# Alimentacion.net
KiCad netlist of a schematic drawn in Altium Designer
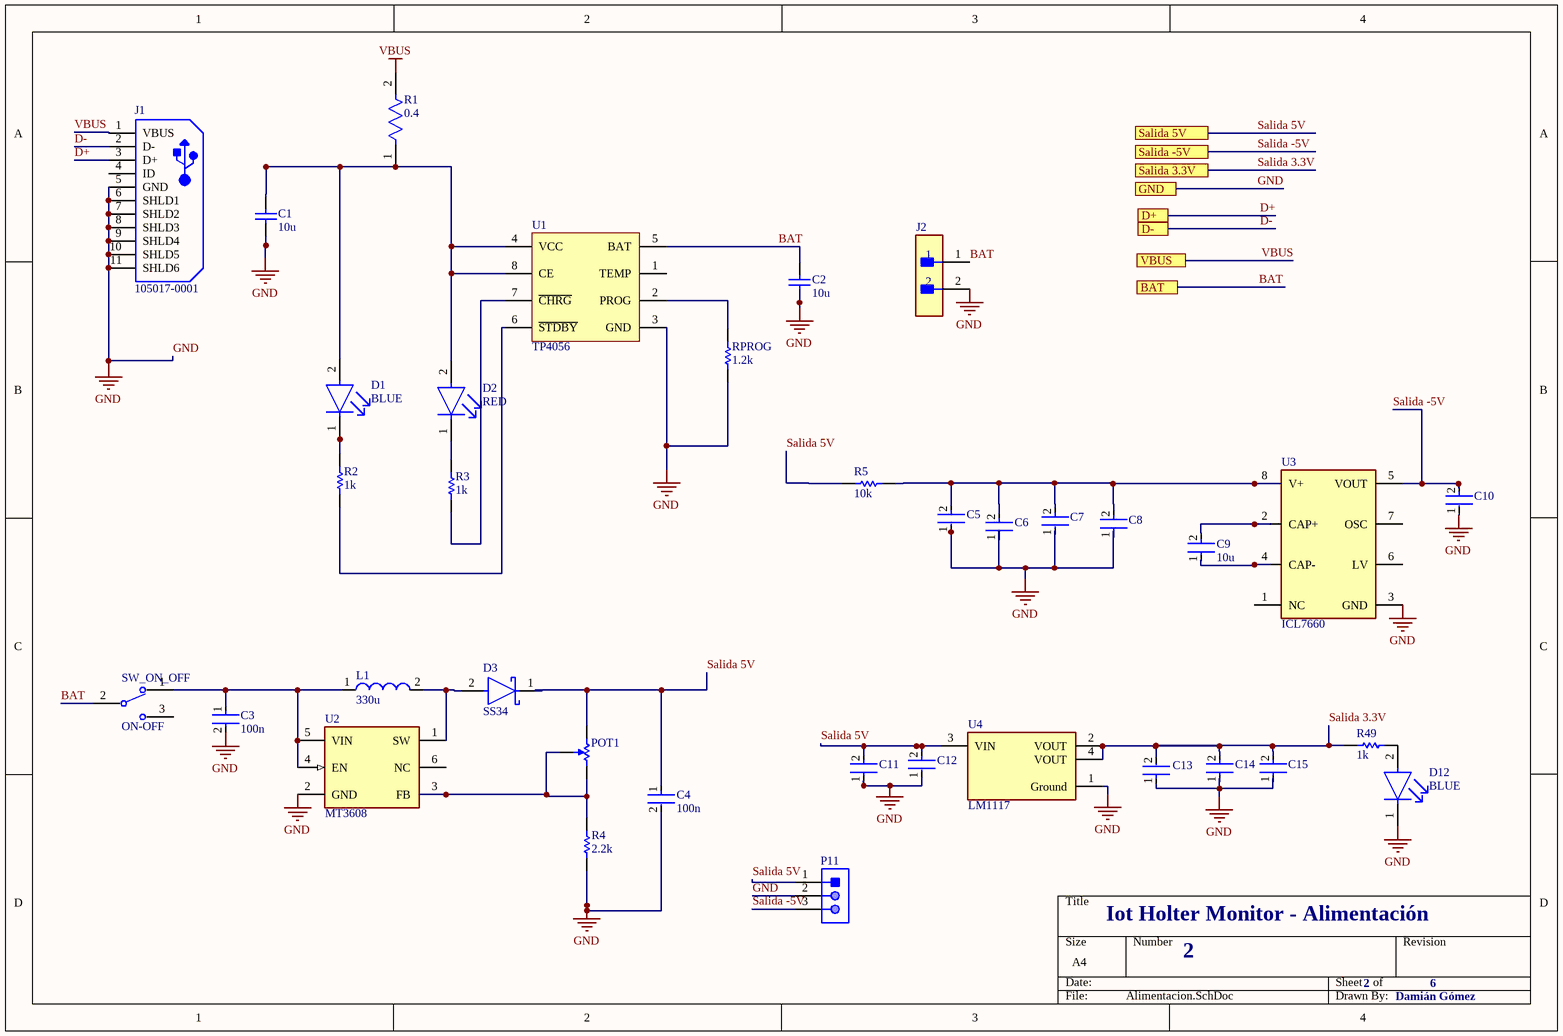
[diagram p0: Alimentacion.SchDoc]

(export (version "E")
  (design (tool "Eeschema 10.0.6"))
  (components
    (comp (ref "C1")
      (value "10u")
      (footprint "KEMT-1206-2_M")
      (description "CAP, Ceramic, 0.1 uF, +/- 10%, 50 V, -55 to 125 degC, 1206 (3216 Metric), RoHS, Tape and Reel")
      (fields (field (name "MANUFACTURER") "Kemet"))
      (libsource (lib "Altium Content Vault") (part "CAP-NP-2"))
    )
    (comp (ref "C2")
      (value "10u")
      (footprint "CAPC3216X190X55LL30T25")
      (description "Chip Capacitor, 10 uF, +/- 20%, 6.3 V, -55 to 85 degC, 1206 (3216 Metric), RoHS, Tape and Reel")
      (fields (field (name "TOLERANCE") "20%") (field (name "PARTNUMBER") "GRM31CR60J107ME39L"))
      (libsource (lib "Altium Content Vault") (part "CAP-NP-2"))
    )
    (comp (ref "C3")
      (value "100n")
      (footprint "FP-CL31-IPC_C")
      (description "Cap Ceramic 100nF 500V C0G ±5% SMD 1206 +125°C Embossed T/R")
      (fields (field (name "TOLERANCE") "5%"))
      (libsource (lib "Altium Content Vault") (part "b4654b650e69147ec39a6b967a45e02"))
    )
    (comp (ref "C4")
      (value "100n")
      (footprint "FP-CL31-IPC_C")
      (description "Cap Ceramic 100nF 500V C0G ±5% SMD 1206 +125°C Embossed T/R")
      (fields (field (name "TOLERANCE") "5%"))
      (libsource (lib "Altium Content Vault") (part "b4654b650e69147ec39a6b967a45e02"))
    )
    (comp (ref "C5")
      (value "GRM2165C1H332JA01D")
      (footprint "FP-GRM216-0_1-IPC_B")
      (description "Chip Multilayer Ceramic Capacitors for General Purpose, 0805, 3300pF, C0G, 30ppm/°C, 5%, 50V")
      (fields (field (name "VOLTAGE") "50V") (field (name "TOLERANCE") "5%"))
      (libsource (lib "Altium Content Vault") (part "236180d848d6139a670b325ea6854c9"))
    )
    (comp (ref "C6")
      (value "GRM2165C1H332JA01D")
      (footprint "FP-GRM216-0_1-IPC_B")
      (description "Chip Multilayer Ceramic Capacitors for General Purpose, 0805, 3300pF, C0G, 30ppm/°C, 5%, 50V")
      (fields (field (name "VOLTAGE") "50V") (field (name "TOLERANCE") "5%"))
      (libsource (lib "Altium Content Vault") (part "236180d848d6139a670b325ea6854c9"))
    )
    (comp (ref "C7")
      (value "GRM2165C1H332JA01D")
      (footprint "FP-GRM216-0_1-IPC_B")
      (description "Chip Multilayer Ceramic Capacitors for General Purpose, 0805, 3300pF, C0G, 30ppm/°C, 5%, 50V")
      (fields (field (name "VOLTAGE") "50V") (field (name "TOLERANCE") "5%"))
      (libsource (lib "Altium Content Vault") (part "236180d848d6139a670b325ea6854c9"))
    )
    (comp (ref "C8")
      (value "GRM2165C1H332JA01D")
      (footprint "FP-GRM216-0_1-IPC_B")
      (description "Chip Multilayer Ceramic Capacitors for General Purpose, 0805, 3300pF, C0G, 30ppm/°C, 5%, 50V")
      (fields (field (name "VOLTAGE") "50V") (field (name "TOLERANCE") "5%"))
      (libsource (lib "Altium Content Vault") (part "236180d848d6139a670b325ea6854c9"))
    )
    (comp (ref "C9")
      (value "10u")
      (footprint "FP-GRM216-0_1-IPC_B")
      (description "Chip Multilayer Ceramic Capacitors for General Purpose, 0805, 3300pF, C0G, 30ppm/°C, 5%, 50V")
      (fields (field (name "VOLTAGE") "50V") (field (name "TOLERANCE") "5%"))
      (libsource (lib "Altium Content Vault") (part "236180d848d6139a670b325ea6854c9"))
    )
    (comp (ref "C10")
      (value "GRM2165C1H332JA01D")
      (footprint "FP-GRM216-0_1-IPC_B")
      (description "Chip Multilayer Ceramic Capacitors for General Purpose, 0805, 3300pF, C0G, 30ppm/°C, 5%, 50V")
      (fields (field (name "VOLTAGE") "50V") (field (name "TOLERANCE") "5%"))
      (libsource (lib "Altium Content Vault") (part "236180d848d6139a670b325ea6854c9"))
    )
    (comp (ref "C11")
      (value "GRM2165C1H332JA01D")
      (footprint "FP-GRM216-0_1-IPC_B")
      (description "Chip Multilayer Ceramic Capacitors for General Purpose, 0805, 3300pF, C0G, 30ppm/°C, 5%, 50V")
      (fields (field (name "VOLTAGE") "50V") (field (name "TOLERANCE") "5%"))
      (libsource (lib "Altium Content Vault") (part "236180d848d6139a670b325ea6854c9"))
    )
    (comp (ref "C12")
      (value "GRM2165C1H332JA01D")
      (footprint "FP-GRM216-0_1-IPC_B")
      (description "Chip Multilayer Ceramic Capacitors for General Purpose, 0805, 3300pF, C0G, 30ppm/°C, 5%, 50V")
      (fields (field (name "VOLTAGE") "50V") (field (name "TOLERANCE") "5%"))
      (libsource (lib "Altium Content Vault") (part "236180d848d6139a670b325ea6854c9"))
    )
    (comp (ref "C13")
      (value "10uF")
      (footprint "FP-CL31-IPC_C")
      (description "Cap Ceramic 10uF 500V C0G ±5% SMD 1206 +125°C Embossed T/R")
      (fields (field (name "TOLERANCE") "5%"))
      (libsource (lib "Altium Content Vault") (part "b4654b650e69147ec39a6b967a45e02"))
    )
    (comp (ref "C14")
      (value "GRM2165C1H332JA01D")
      (footprint "FP-GRM216-0_1-IPC_C")
      (description "Chip Multilayer Ceramic Capacitors for General Purpose, 0805, 3300pF, C0G, 30ppm/°C, 5%, 50V")
      (fields (field (name "VOLTAGE") "50V") (field (name "TOLERANCE") "5%"))
      (libsource (lib "Altium Content Vault") (part "236180d848d6139a670b325ea6854c9"))
    )
    (comp (ref "C15")
      (value "GRM2165C1H332JA01D")
      (footprint "FP-GRM216-0_1-IPC_C")
      (description "Chip Multilayer Ceramic Capacitors for General Purpose, 0805, 3300pF, C0G, 30ppm/°C, 5%, 50V")
      (fields (field (name "VOLTAGE") "50V") (field (name "TOLERANCE") "5%"))
      (libsource (lib "Altium Content Vault") (part "236180d848d6139a670b325ea6854c9"))
    )
    (comp (ref "D1")
      (value "BLUE")
      (footprint "FP-LTST-C191TBKT-MFG")
      (description "LED BLUE CLEAR CHIP SMD")
      (libsource (lib "Altium Content Vault") (part "8706943c75ba83719d021d2fdc84c58"))
    )
    (comp (ref "D2")
      (value "RED")
      (footprint "FP-LTST-C191TBKT-MFG")
      (description "LED BLUE CLEAR CHIP SMD")
      (libsource (lib "Altium Content Vault") (part "8706943c75ba83719d021d2fdc84c58"))
    )
    (comp (ref "D3")
      (value "SS34")
      (footprint "FP-95402-MFG")
      (description "DIODE SCHOTTKY 40V 3A DO214AB")
      (fields (field (name "MANUFACTURER") "Vishay") (field (name "MANUFACTURER PART NUMBER") "SS34-E3/57T"))
      (libsource (lib "Altium Content Vault") (part "1d6ec82d83fb6aee721767c19dac4b9"))
    )
    (comp (ref "D12")
      (value "BLUE")
      (footprint "FP-LTST-C191TBKT-MFG")
      (description "LED BLUE CLEAR CHIP SMD")
      (libsource (lib "Altium Content Vault") (part "8706943c75ba83719d021d2fdc84c58"))
    )
    (comp (ref "J1")
      (value "105017-0001")
      (footprint "USB-MICRO-B_V")
      (fields (field (name "MANUFACTURER") "Molex"))
      (libsource (lib "Altium Content Vault") (part "USB-5-6SHLD"))
    )
    (comp (ref "J2")
      (value "TSW-102-07-L-S")
      (footprint "FP-TSW-102-07-L-S-MFG")
      (description "CONN HEADER VERT 2POS 2.54MM")
      (libsource (lib "Altium Content Vault") (part "3bc925449376181038e59eaffc5286c"))
    )
    (comp (ref "L1")
      (value "330u")
      (footprint "WE-PD 1050")
      (description "SMD-Shielded Power Inductor WE-PD, L=330 µH")
      (fields (field (name "MANUFACTURER") "Wuerth Elektronik") (field (name "PARTNUMBER") "7447714331"))
      (libsource (lib "Altium Content Vault") (part "PAS-IND-INDUCTOR-2"))
    )
    (comp (ref "P11")
      (value "640456-3")
      (footprint "TECO-640456-3")
      (description "Male Header, Pitch 2.54 mm, 1 x 3 Position, Height 10.03 mm, Tail Length 3.56 mm, -55 to 105 degC")
      (fields (field (name "MANUFACTURER") "TE Connectivity"))
      (libsource (lib "Altium Content Vault") (part "CN-1P-M-R3"))
    )
    (comp (ref "POT1")
      (value "3386P-1-104LF")
      (footprint "BOUR-3386P")
      (fields (field (name "TOLERANCE") "10%") (field (name "MANUFACTURER") "Bourns"))
      (libsource (lib "Altium Content Vault") (part "RES-ADJ-3_A"))
    )
    (comp (ref "R1")
      (value "0.4")
      (footprint "FP-RC3216-MFG")
      (description "Res Thick Film 1206 1kΩ 5% 0.25W ±100ppm/°C Molded SMD T/R")
      (fields (field (name "TOLERANCE") "5%"))
      (libsource (lib "Altium Content Vault") (part "1029c3af85768c4190bb7ad29bc67b5"))
    )
    (comp (ref "R2")
      (value "1k")
      (footprint "RESC2013X50X30LL20T20")
      (fields (field (name "MANUFACTURER") "Vishay Dale") (field (name "PART NUMBER") "CRCW08050000Z0EA"))
      (libsource (lib "Altium Content Vault") (part "RES"))
    )
    (comp (ref "R3")
      (value "1k")
      (footprint "RESC2013X50X30LL20T20")
      (fields (field (name "MANUFACTURER") "Vishay Dale") (field (name "PART NUMBER") "CRCW08050000Z0EA"))
      (libsource (lib "Altium Content Vault") (part "RES"))
    )
    (comp (ref "R4")
      (value "2.2k")
      (footprint "RESC2013X50X30LL20T20")
      (fields (field (name "MANUFACTURER") "Vishay Dale") (field (name "PART NUMBER") "CRCW08050000Z0EA"))
      (libsource (lib "Altium Content Vault") (part "RES"))
    )
    (comp (ref "R5")
      (value "10k")
      (footprint "RESC2013X50X30LL20T20")
      (fields (field (name "MANUFACTURER") "Vishay Dale") (field (name "PART NUMBER") "CRCW08050000Z0EA"))
      (libsource (lib "Altium Content Vault") (part "RES"))
    )
    (comp (ref "R49")
      (value "1k")
      (footprint "RESC2013X50X30LL20T20")
      (fields (field (name "MANUFACTURER") "Vishay Dale") (field (name "PART NUMBER") "CRCW08050000Z0EA"))
      (libsource (lib "Altium Content Vault") (part "RES"))
    )
    (comp (ref "RPROG")
      (value "1.2k")
      (footprint "RESC2013X50X30LL20T20")
      (fields (field (name "MANUFACTURER") "Vishay Dale") (field (name "PART NUMBER") "CRCW08050000Z0EA"))
      (libsource (lib "Altium Content Vault") (part "RES"))
    )
    (comp (ref "SW_ON_OFF")
      (value "ON-OFF")
      (footprint "FP-1825115-1-MFG")
      (description "SWITCH SLIDE SPDT 250MA 125V")
      (fields
        (field (name "MANUFACTURER PART NUMBER") "1825115-1")
        (field (name "MANUFACTURER") "TE Connectivity")
      )
      (libsource (lib "Altium Content Vault") (part "ec4e4964ed0d2d669af15d5af94fda9"))
    )
    (comp (ref "U1")
      (value "TP4056")
      (footprint "LT-S8-8_N")
      (fields
        (field (name "MANUFACTURER") "Linear Technology")
        (field (name "PARTNUMBER") "LTC4002ES8-4.2#PBF")
      )
      (libsource (lib "Altium Content Vault") (part "LT-LTC4002-X-S8-8"))
    )
    (comp (ref "U2")
      (value "MT3608")
      (footprint "FP-SOT26_SC74R-MFG")
      (description "IC LED DRIVER RGLTR DIM SOT23-6")
      (fields
        (field (name "MANUFACTURER PART NUMBER") "AP3032KTR-G1")
        (field (name "OCTOPART") "https://octopart.com/ap3032ktr-g1-diodes+inc.-30954666")
      )
      (libsource (lib "Altium Content Vault") (part "3919cb25f4a0d6df43ad4561642b66f"))
    )
    (comp (ref "U3")
      (value "ICL7660")
      (footprint "FP-S8-4-MFG")
      (description "IC REG CHARG PUMP INV 20MA 8SOIC")
      (fields
        (field (name "MANUFACTURER PART NUMBER") "ICL7660ESA+")
        (field (name "MANUFACTURER") "Maxim Integrated")
      )
      (libsource (lib "Altium Content Vault") (part "e56b1e088fdcf266b110f64408d959f"))
    )
    (comp (ref "U4")
      (value "LM1117")
      (footprint "FP-AMS1117-IPC_C")
      (description "LDO Voltage Regulators 1A, 3.3V")
      (fields
        (field (name "MANUFACTURER PART NUMBER") "AMS1117-3.3")
        (field (name "OCTOPART") "https://octopart.com/ams1117-3.3-advanced+monolithic+systems-25899300")
      )
      (libsource (lib "Altium Content Vault") (part "8bdbb5f8e77002000e30dd2845d0354"))
    )
  )
  (nets
    (net (code "1") (name "/BAT") (class "Default")
      (node (ref "C2") (pin "2") (pinfunction "2_2") (pintype "passive"))
      (node (ref "J2") (pin "1") (pinfunction "1_1") (pintype "passive"))
      (node (ref "SW_ON_OFF") (pin "2") (pinfunction "2_2") (pintype "passive"))
      (node (ref "U1") (pin "5") (pinfunction "BAT_5") (pintype "passive"))
    )
    (net (code "2") (name "/D+") (class "Default")
      (node (ref "J1") (pin "3") (pinfunction "D+_3") (pintype "tri_state"))
    )
    (net (code "3") (name "/D-") (class "Default")
      (node (ref "J1") (pin "2") (pinfunction "D-_2") (pintype "tri_state"))
    )
    (net (code "4") (name "/Salida -5V") (class "Default")
      (node (ref "C10") (pin "2") (pinfunction "2_2") (pintype "passive"))
      (node (ref "P11") (pin "3") (pinfunction "3_3") (pintype "passive"))
      (node (ref "U3") (pin "5") (pinfunction "VOUT_5") (pintype "power_in"))
    )
    (net (code "5") (name "/Salida 3.3V") (class "Default")
      (node (ref "C13") (pin "2") (pinfunction "2_2") (pintype "passive"))
      (node (ref "C14") (pin "2") (pinfunction "2_2") (pintype "passive"))
      (node (ref "C15") (pin "2") (pinfunction "2_2") (pintype "passive"))
      (node (ref "R49") (pin "1") (pinfunction "1_1") (pintype "passive"))
      (node (ref "U4") (pin "2") (pinfunction "VOUT_2") (pintype "power_in"))
      (node (ref "U4") (pin "4") (pinfunction "VOUT_4") (pintype "power_in"))
    )
    (net (code "6") (name "/Salida 5V") (class "Default")
      (node (ref "C11") (pin "2") (pinfunction "2_2") (pintype "passive"))
      (node (ref "C12") (pin "2") (pinfunction "2_2") (pintype "passive"))
      (node (ref "C4") (pin "1") (pinfunction "1_1") (pintype "passive"))
      (node (ref "D3") (pin "1") (pinfunction "C_1") (pintype "passive"))
      (node (ref "P11") (pin "1") (pinfunction "1_1") (pintype "passive"))
      (node (ref "POT1") (pin "1") (pinfunction "1_1") (pintype "passive"))
      (node (ref "R5") (pin "1") (pinfunction "1_1") (pintype "passive"))
      (node (ref "U4") (pin "3") (pinfunction "VIN_3") (pintype "power_in"))
    )
    (net (code "7") (name "GND") (class "Default")
      (node (ref "C1") (pin "1") (pinfunction "1_1") (pintype "passive"))
      (node (ref "C10") (pin "1") (pinfunction "1_1") (pintype "passive"))
      (node (ref "C11") (pin "1") (pinfunction "1_1") (pintype "passive"))
      (node (ref "C12") (pin "1") (pinfunction "1_1") (pintype "passive"))
      (node (ref "C13") (pin "1") (pinfunction "1_1") (pintype "passive"))
      (node (ref "C14") (pin "1") (pinfunction "1_1") (pintype "passive"))
      (node (ref "C15") (pin "1") (pinfunction "1_1") (pintype "passive"))
      (node (ref "C2") (pin "1") (pinfunction "1_1") (pintype "passive"))
      (node (ref "C3") (pin "2") (pinfunction "2_2") (pintype "passive"))
      (node (ref "C4") (pin "2") (pinfunction "2_2") (pintype "passive"))
      (node (ref "C5") (pin "1") (pinfunction "1_1") (pintype "passive"))
      (node (ref "C6") (pin "1") (pinfunction "1_1") (pintype "passive"))
      (node (ref "C7") (pin "1") (pinfunction "1_1") (pintype "passive"))
      (node (ref "C8") (pin "1") (pinfunction "1_1") (pintype "passive"))
      (node (ref "D12") (pin "1") (pinfunction "C_1") (pintype "passive"))
      (node (ref "J1") (pin "10") (pinfunction "SHLD5_10") (pintype "passive"))
      (node (ref "J1") (pin "11") (pinfunction "SHLD6_11") (pintype "passive"))
      (node (ref "J1") (pin "5") (pinfunction "GND_5") (pintype "passive"))
      (node (ref "J1") (pin "6") (pinfunction "SHLD1_6") (pintype "passive"))
      (node (ref "J1") (pin "7") (pinfunction "SHLD2_7") (pintype "passive"))
      (node (ref "J1") (pin "8") (pinfunction "SHLD3_8") (pintype "passive"))
      (node (ref "J1") (pin "9") (pinfunction "SHLD4_9") (pintype "passive"))
      (node (ref "J2") (pin "2") (pinfunction "2_2") (pintype "passive"))
      (node (ref "P11") (pin "2") (pinfunction "2_2") (pintype "passive"))
      (node (ref "R4") (pin "1") (pinfunction "1_1") (pintype "passive"))
      (node (ref "RPROG") (pin "1") (pinfunction "1_1") (pintype "passive"))
      (node (ref "U1") (pin "3") (pinfunction "GND_3") (pintype "passive"))
      (node (ref "U2") (pin "2") (pinfunction "GND_2") (pintype "passive"))
      (node (ref "U3") (pin "3") (pinfunction "GND_3") (pintype "passive"))
      (node (ref "U4") (pin "1") (pinfunction "Ground_1") (pintype "passive"))
    )
    (net (code "8") (name "Net-(D1-A)") (class "Default")
      (node (ref "C1") (pin "2") (pinfunction "2_2") (pintype "passive"))
      (node (ref "D1") (pin "2") (pinfunction "A_2") (pintype "passive"))
      (node (ref "D2") (pin "2") (pinfunction "A_2") (pintype "passive"))
      (node (ref "R1") (pin "1") (pinfunction "1_1") (pintype "passive"))
      (node (ref "U1") (pin "4") (pinfunction "VCC_4") (pintype "passive"))
      (node (ref "U1") (pin "8") (pinfunction "CE_8") (pintype "passive"))
    )
    (net (code "9") (name "Net-(D1-C)") (class "Default")
      (node (ref "D1") (pin "1") (pinfunction "C_1") (pintype "passive"))
      (node (ref "R2") (pin "2") (pinfunction "2_2") (pintype "passive"))
    )
    (net (code "10") (name "Net-(D2-C)") (class "Default")
      (node (ref "D2") (pin "1") (pinfunction "C_1") (pintype "passive"))
      (node (ref "R3") (pin "2") (pinfunction "2_2") (pintype "passive"))
    )
    (net (code "11") (name "Net-(D3-A)") (class "Default")
      (node (ref "D3") (pin "2") (pinfunction "A_2") (pintype "passive"))
      (node (ref "L1") (pin "2") (pinfunction "2_2") (pintype "passive"))
      (node (ref "U2") (pin "1") (pinfunction "SW_1") (pintype "passive"))
    )
    (net (code "12") (name "Net-(D12-A)") (class "Default")
      (node (ref "D12") (pin "2") (pinfunction "A_2") (pintype "passive"))
      (node (ref "R49") (pin "2") (pinfunction "2_2") (pintype "passive"))
    )
    (net (code "13") (name "Net-(U1-PROG)") (class "Default")
      (node (ref "RPROG") (pin "2") (pinfunction "2_2") (pintype "passive"))
      (node (ref "U1") (pin "2") (pinfunction "PROG_2") (pintype "passive"))
    )
    (net (code "14") (name "Net-(U1-~{CHRG})") (class "Default")
      (node (ref "R3") (pin "1") (pinfunction "1_1") (pintype "passive"))
      (node (ref "U1") (pin "7") (pinfunction "~{CHRG}_7") (pintype "passive"))
    )
    (net (code "15") (name "Net-(U1-~{STDBY})") (class "Default")
      (node (ref "R2") (pin "1") (pinfunction "1_1") (pintype "passive"))
      (node (ref "U1") (pin "6") (pinfunction "~{STDBY}_6") (pintype "passive"))
    )
    (net (code "16") (name "Net-(U2-EN)") (class "Default")
      (node (ref "C3") (pin "1") (pinfunction "1_1") (pintype "passive"))
      (node (ref "L1") (pin "1") (pinfunction "1_1") (pintype "passive"))
      (node (ref "SW_ON_OFF") (pin "1") (pinfunction "1_1") (pintype "passive"))
      (node (ref "U2") (pin "4") (pinfunction "EN_4") (pintype "input"))
      (node (ref "U2") (pin "5") (pinfunction "VIN_5") (pintype "power_in"))
    )
    (net (code "17") (name "Net-(U2-FB)") (class "Default")
      (node (ref "POT1") (pin "2") (pinfunction "2_2") (pintype "passive"))
      (node (ref "POT1") (pin "3") (pinfunction "3_3") (pintype "passive"))
      (node (ref "R4") (pin "2") (pinfunction "2_2") (pintype "passive"))
      (node (ref "U2") (pin "3") (pinfunction "FB_3") (pintype "power_in"))
    )
    (net (code "18") (name "Net-(U3-CAP+)") (class "Default")
      (node (ref "C9") (pin "2") (pinfunction "2_2") (pintype "passive"))
      (node (ref "U3") (pin "2") (pinfunction "CAP+_2") (pintype "power_in"))
    )
    (net (code "19") (name "Net-(U3-CAP-)") (class "Default")
      (node (ref "C9") (pin "1") (pinfunction "1_1") (pintype "passive"))
      (node (ref "U3") (pin "4") (pinfunction "CAP-_4") (pintype "power_in"))
    )
    (net (code "20") (name "Net-(U3-V+)") (class "Default")
      (node (ref "C5") (pin "2") (pinfunction "2_2") (pintype "passive"))
      (node (ref "C6") (pin "2") (pinfunction "2_2") (pintype "passive"))
      (node (ref "C7") (pin "2") (pinfunction "2_2") (pintype "passive"))
      (node (ref "C8") (pin "2") (pinfunction "2_2") (pintype "passive"))
      (node (ref "R5") (pin "2") (pinfunction "2_2") (pintype "passive"))
      (node (ref "U3") (pin "8") (pinfunction "V+_8") (pintype "power_in"))
    )
    (net (code "21") (name "VBUS") (class "Default")
      (node (ref "J1") (pin "1") (pinfunction "VBUS_1") (pintype "passive"))
      (node (ref "R1") (pin "2") (pinfunction "2_2") (pintype "passive"))
    )
    (net (code "22") (name "unconnected-(J1-ID-Pad4)") (class "Default")
      (node (ref "J1") (pin "4") (pinfunction "ID_4") (pintype "passive"))
    )
    (net (code "23") (name "unconnected-(SW_ON_OFF-Pad3)") (class "Default")
      (node (ref "SW_ON_OFF") (pin "3") (pinfunction "3_3") (pintype "passive"))
    )
    (net (code "24") (name "unconnected-(U1-TEMP-Pad1)") (class "Default")
      (node (ref "U1") (pin "1") (pinfunction "TEMP_1") (pintype "passive"))
    )
    (net (code "25") (name "unconnected-(U2-NC-Pad6)") (class "Default")
      (node (ref "U2") (pin "6") (pinfunction "NC_6") (pintype "passive"))
    )
    (net (code "26") (name "unconnected-(U3-LV-Pad6)") (class "Default")
      (node (ref "U3") (pin "6") (pinfunction "LV_6") (pintype "passive"))
    )
    (net (code "27") (name "unconnected-(U3-NC-Pad1)") (class "Default")
      (node (ref "U3") (pin "1") (pinfunction "NC_1") (pintype "passive"))
    )
    (net (code "28") (name "unconnected-(U3-OSC-Pad7)") (class "Default")
      (node (ref "U3") (pin "7") (pinfunction "OSC_7") (pintype "passive"))
    )
  )
)
